# KidSize.net
KiCad netlist of a schematic drawn in EAGLE
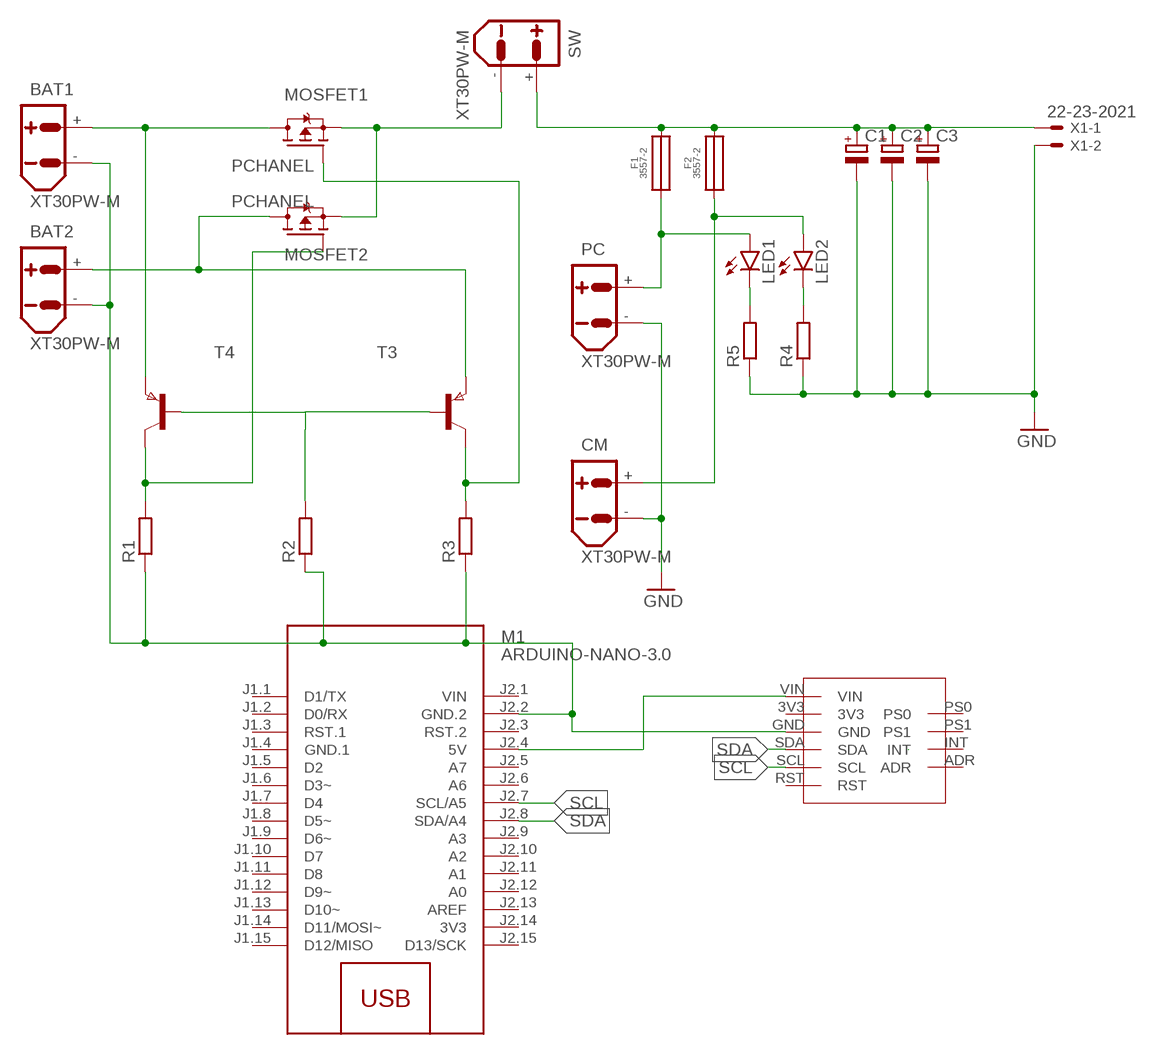
[diagram p0: schematic, sheet 1]

(export (version "E")
  (design (tool "Eeschema 10.0.6"))
  (components
    (comp (ref "BAT1")
      (value "XT30PW-M")
      (footprint "eagle-import:XT30PW-M")
      (libsource (lib "eagle-import") (part "XT30PW-M"))
    )
    (comp (ref "BAT2")
      (value "XT30PW-M")
      (footprint "eagle-import:XT30PW-M")
      (libsource (lib "eagle-import") (part "XT30PW-M"))
    )
    (comp (ref "C1")
      (value "CPOL-EU150CLZ-1014")
      (footprint "eagle-import:150CLZ-1014")
      (libsource (lib "eagle-import") (part "CPOL-EU150CLZ-1014"))
    )
    (comp (ref "C2")
      (value "CPOL-EU150CLZ-1014")
      (footprint "eagle-import:150CLZ-1014")
      (libsource (lib "eagle-import") (part "CPOL-EU150CLZ-1014"))
    )
    (comp (ref "C3")
      (value "CPOL-EU150CLZ-1014")
      (footprint "eagle-import:150CLZ-1014")
      (libsource (lib "eagle-import") (part "CPOL-EU150CLZ-1014"))
    )
    (comp (ref "CM")
      (value "XT30PW-M")
      (footprint "eagle-import:XT30PW-M")
      (libsource (lib "eagle-import") (part "XT30PW-M"))
    )
    (comp (ref "F1")
      (value "3557-2")
      (footprint "eagle-import:3557-2")
      (libsource (lib "eagle-import") (part "3557-2"))
    )
    (comp (ref "F2")
      (value "3557-2")
      (footprint "eagle-import:3557-2")
      (libsource (lib "eagle-import") (part "3557-2"))
    )
    (comp (ref "LED1")
      (value "LEDCHIP-LED0805")
      (footprint "eagle-import:CHIP-LED0805")
      (libsource (lib "eagle-import") (part "LEDCHIP-LED0805"))
    )
    (comp (ref "LED2")
      (value "LEDCHIP-LED0805")
      (footprint "eagle-import:CHIP-LED0805")
      (libsource (lib "eagle-import") (part "LEDCHIP-LED0805"))
    )
    (comp (ref "M1")
      (value "ARDUINO-NANO-3.0")
      (footprint "eagle-import:ARDUINO-NANO-3.0")
      (libsource (lib "eagle-import") (part "ARDUINO-NANO-3.0"))
    )
    (comp (ref "MOSFET1")
      (value "PCHANEL")
      (footprint "eagle-import:TO252")
      (libsource (lib "eagle-import") (part "FDD4141TO252"))
    )
    (comp (ref "MOSFET2")
      (value "PCHANEL")
      (footprint "eagle-import:TO252")
      (libsource (lib "eagle-import") (part "FDD4141TO252"))
    )
    (comp (ref "PC")
      (value "XT30PW-M")
      (footprint "eagle-import:XT30PW-M")
      (libsource (lib "eagle-import") (part "XT30PW-M"))
    )
    (comp (ref "R1")
      (value "R-EU_R1206")
      (footprint "eagle-import:R1206")
      (libsource (lib "eagle-import") (part "R-EU_R1206"))
    )
    (comp (ref "R2")
      (value "R-EU_R1206")
      (footprint "eagle-import:R1206")
      (libsource (lib "eagle-import") (part "R-EU_R1206"))
    )
    (comp (ref "R3")
      (value "R-EU_R1206")
      (footprint "eagle-import:R1206")
      (libsource (lib "eagle-import") (part "R-EU_R1206"))
    )
    (comp (ref "R4")
      (value "R-EU_M0805")
      (footprint "eagle-import:M0805")
      (libsource (lib "eagle-import") (part "R-EU_M0805"))
    )
    (comp (ref "R5")
      (value "R-EU_M0805")
      (footprint "eagle-import:M0805")
      (libsource (lib "eagle-import") (part "R-EU_M0805"))
    )
    (comp (ref "SW")
      (value "XT30PW-M")
      (footprint "eagle-import:XT30PW-M")
      (libsource (lib "eagle-import") (part "XT30PW-M"))
    )
    (comp (ref "T3")
      (value "PNPSOT23")
      (footprint "eagle-import:SOT-23")
      (fields (field (name "MPN") "DSS20200L-7"))
      (libsource (lib "eagle-import") (part "PNPSOT23"))
    )
    (comp (ref "T4")
      (value "PNPSOT23")
      (footprint "eagle-import:SOT-23")
      (fields (field (name "MPN") "DSS20200L-7"))
      (libsource (lib "eagle-import") (part "PNPSOT23"))
    )
    (comp (ref "U$1")
      (value "BNO055_BNO055")
      (footprint "eagle-import:BNO055_BNO055")
      (libsource (lib "eagle-import") (part "BNO055_BNO055"))
    )
    (comp (ref "X1")
      (value "22-23-2021")
      (footprint "eagle-import:22-23-2021")
      (fields (field (name "MF") "MOLEX"))
      (libsource (lib "eagle-import") (part "22-23-2021"))
    )
  )
  (nets
    (net (code "1") (name "/3V3") (class "Default")
      (node (ref "M1") (pin "J2.14") (pinfunction "3V3_J2.14") (pintype "power_in"))
    )
    (net (code "2") (name "/GND.1") (class "Default")
      (node (ref "M1") (pin "J1.4") (pinfunction "GND.1_J1.4") (pintype "power_in"))
    )
    (net (code "3") (name "/VIN") (class "Default")
      (node (ref "M1") (pin "J2.1") (pinfunction "VIN_J2.1") (pintype "power_in"))
    )
    (net (code "4") (name "GND") (class "Default")
      (node (ref "BAT1") (pin "-") (pinfunction "-_-") (pintype "power_in"))
      (node (ref "BAT2") (pin "-") (pinfunction "-_-") (pintype "power_in"))
      (node (ref "C1") (pin "-") (pinfunction "-_-") (pintype "passive"))
      (node (ref "C2") (pin "-") (pinfunction "-_-") (pintype "passive"))
      (node (ref "C3") (pin "-") (pinfunction "-_-") (pintype "passive"))
      (node (ref "CM") (pin "-") (pinfunction "-_-") (pintype "power_in"))
      (node (ref "M1") (pin "J2.2") (pinfunction "GND.2_J2.2") (pintype "power_in"))
      (node (ref "PC") (pin "-") (pinfunction "-_-") (pintype "power_in"))
      (node (ref "R1") (pin "1") (pinfunction "1_1") (pintype "passive"))
      (node (ref "R2") (pin "1") (pinfunction "1_1") (pintype "passive"))
      (node (ref "R3") (pin "1") (pinfunction "1_1") (pintype "passive"))
      (node (ref "R4") (pin "1") (pinfunction "1_1") (pintype "passive"))
      (node (ref "R5") (pin "1") (pinfunction "1_1") (pintype "passive"))
      (node (ref "U$1") (pin "GND") (pinfunction "GND_GND") (pintype "bidirectional"))
      (node (ref "X1") (pin "2") (pinfunction "S_2") (pintype "passive"))
    )
    (net (code "5") (name "Net-(CM-Pad+)") (class "Default")
      (node (ref "CM") (pin "+") (pinfunction "+_+") (pintype "power_in"))
      (node (ref "F2") (pin "1") (pinfunction "1_1") (pintype "bidirectional"))
      (node (ref "F2") (pin "2") (pinfunction "1_2") (pintype "bidirectional"))
      (node (ref "LED2") (pin "A") (pinfunction "A_A") (pintype "passive"))
    )
    (net (code "6") (name "Net-(F1-1-Pad2)") (class "Default")
      (node (ref "F1") (pin "1") (pinfunction "1_1") (pintype "bidirectional"))
      (node (ref "F1") (pin "2") (pinfunction "1_2") (pintype "bidirectional"))
      (node (ref "LED1") (pin "A") (pinfunction "A_A") (pintype "passive"))
      (node (ref "PC") (pin "+") (pinfunction "+_+") (pintype "power_in"))
    )
    (net (code "7") (name "Net-(LED1-PadC)") (class "Default")
      (node (ref "LED1") (pin "C") (pinfunction "C_C") (pintype "passive"))
      (node (ref "R5") (pin "2") (pinfunction "2_2") (pintype "passive"))
    )
    (net (code "8") (name "Net-(LED2-PadC)") (class "Default")
      (node (ref "LED2") (pin "C") (pinfunction "C_C") (pintype "passive"))
      (node (ref "R4") (pin "2") (pinfunction "2_2") (pintype "passive"))
    )
    (net (code "9") (name "Net-(M1-5V)") (class "Default")
      (node (ref "M1") (pin "J2.4") (pinfunction "5V_J2.4") (pintype "power_in"))
      (node (ref "U$1") (pin "VIN") (pinfunction "VIN_VIN") (pintype "bidirectional"))
    )
    (net (code "10") (name "Net-(MOSFET1-D)") (class "Default")
      (node (ref "BAT1") (pin "+") (pinfunction "+_+") (pintype "power_in"))
      (node (ref "MOSFET1") (pin "3") (pinfunction "D_3") (pintype "passive"))
      (node (ref "T4") (pin "2") (pinfunction "E_2") (pintype "passive"))
    )
    (net (code "11") (name "Net-(MOSFET1-G)") (class "Default")
      (node (ref "MOSFET1") (pin "1") (pinfunction "G_1") (pintype "passive"))
      (node (ref "R3") (pin "2") (pinfunction "2_2") (pintype "passive"))
      (node (ref "T3") (pin "1") (pinfunction "C_1") (pintype "passive"))
    )
    (net (code "12") (name "Net-(MOSFET1-S)") (class "Default")
      (node (ref "MOSFET1") (pin "2") (pinfunction "S_2") (pintype "passive"))
      (node (ref "MOSFET2") (pin "2") (pinfunction "S_2") (pintype "passive"))
      (node (ref "SW") (pin "-") (pinfunction "-_-") (pintype "power_in"))
    )
    (net (code "13") (name "Net-(MOSFET2-D)") (class "Default")
      (node (ref "BAT2") (pin "+") (pinfunction "+_+") (pintype "power_in"))
      (node (ref "MOSFET2") (pin "3") (pinfunction "D_3") (pintype "passive"))
      (node (ref "T3") (pin "2") (pinfunction "E_2") (pintype "passive"))
    )
    (net (code "14") (name "Net-(MOSFET2-G)") (class "Default")
      (node (ref "MOSFET2") (pin "1") (pinfunction "G_1") (pintype "passive"))
      (node (ref "R1") (pin "2") (pinfunction "2_2") (pintype "passive"))
      (node (ref "T4") (pin "1") (pinfunction "C_1") (pintype "passive"))
    )
    (net (code "15") (name "Net-(T3-B)") (class "Default")
      (node (ref "R2") (pin "2") (pinfunction "2_2") (pintype "passive"))
      (node (ref "T3") (pin "3") (pinfunction "B_3") (pintype "passive"))
      (node (ref "T4") (pin "3") (pinfunction "B_3") (pintype "passive"))
    )
    (net (code "16") (name "Net-(X1A-S)") (class "Default")
      (node (ref "C1") (pin "+") (pinfunction "+_+") (pintype "passive"))
      (node (ref "C2") (pin "+") (pinfunction "+_+") (pintype "passive"))
      (node (ref "C3") (pin "+") (pinfunction "+_+") (pintype "passive"))
      (node (ref "F1") (pin "3") (pinfunction "2_3") (pintype "bidirectional"))
      (node (ref "F1") (pin "4") (pinfunction "2_4") (pintype "bidirectional"))
      (node (ref "F2") (pin "3") (pinfunction "2_3") (pintype "bidirectional"))
      (node (ref "F2") (pin "4") (pinfunction "2_4") (pintype "bidirectional"))
      (node (ref "SW") (pin "+") (pinfunction "+_+") (pintype "power_in"))
      (node (ref "X1") (pin "1") (pinfunction "S_1") (pintype "passive"))
    )
    (net (code "17") (name "SCL") (class "Default")
      (node (ref "M1") (pin "J2.7") (pinfunction "SCL/A5_J2.7") (pintype "bidirectional"))
      (node (ref "U$1") (pin "SCL") (pinfunction "SCL_SCL") (pintype "bidirectional"))
    )
    (net (code "18") (name "SDA") (class "Default")
      (node (ref "M1") (pin "J2.8") (pinfunction "SDA/A4_J2.8") (pintype "bidirectional"))
      (node (ref "U$1") (pin "SDA") (pinfunction "SDA_SDA") (pintype "bidirectional"))
    )
    (net (code "19") (name "unconnected-(M1-A0-PadJ2.12)") (class "Default")
      (node (ref "M1") (pin "J2.12") (pinfunction "A0_J2.12") (pintype "bidirectional"))
    )
    (net (code "20") (name "unconnected-(M1-A1-PadJ2.11)") (class "Default")
      (node (ref "M1") (pin "J2.11") (pinfunction "A1_J2.11") (pintype "bidirectional"))
    )
    (net (code "21") (name "unconnected-(M1-A2-PadJ2.10)") (class "Default")
      (node (ref "M1") (pin "J2.10") (pinfunction "A2_J2.10") (pintype "bidirectional"))
    )
    (net (code "22") (name "unconnected-(M1-A3-PadJ2.9)") (class "Default")
      (node (ref "M1") (pin "J2.9") (pinfunction "A3_J2.9") (pintype "bidirectional"))
    )
    (net (code "23") (name "unconnected-(M1-A6-PadJ2.6)") (class "Default")
      (node (ref "M1") (pin "J2.6") (pinfunction "A6_J2.6") (pintype "bidirectional"))
    )
    (net (code "24") (name "unconnected-(M1-A7-PadJ2.5)") (class "Default")
      (node (ref "M1") (pin "J2.5") (pinfunction "A7_J2.5") (pintype "bidirectional"))
    )
    (net (code "25") (name "unconnected-(M1-AREF-PadJ2.13)") (class "Default")
      (node (ref "M1") (pin "J2.13") (pinfunction "AREF_J2.13") (pintype "bidirectional"))
    )
    (net (code "26") (name "unconnected-(M1-D0{slash}RX-PadJ1.2)") (class "Default")
      (node (ref "M1") (pin "J1.2") (pinfunction "D0/RX_J1.2") (pintype "bidirectional"))
    )
    (net (code "27") (name "unconnected-(M1-D1{slash}TX-PadJ1.1)") (class "Default")
      (node (ref "M1") (pin "J1.1") (pinfunction "D1/TX_J1.1") (pintype "bidirectional"))
    )
    (net (code "28") (name "unconnected-(M1-D2-PadJ1.5)") (class "Default")
      (node (ref "M1") (pin "J1.5") (pinfunction "D2_J1.5") (pintype "bidirectional"))
    )
    (net (code "29") (name "unconnected-(M1-D3~{}-PadJ1.6)") (class "Default")
      (node (ref "M1") (pin "J1.6") (pinfunction "D3~{}_J1.6") (pintype "bidirectional"))
    )
    (net (code "30") (name "unconnected-(M1-D4-PadJ1.7)") (class "Default")
      (node (ref "M1") (pin "J1.7") (pinfunction "D4_J1.7") (pintype "bidirectional"))
    )
    (net (code "31") (name "unconnected-(M1-D5~{}-PadJ1.8)") (class "Default")
      (node (ref "M1") (pin "J1.8") (pinfunction "D5~{}_J1.8") (pintype "bidirectional"))
    )
    (net (code "32") (name "unconnected-(M1-D6~{}-PadJ1.9)") (class "Default")
      (node (ref "M1") (pin "J1.9") (pinfunction "D6~{}_J1.9") (pintype "bidirectional"))
    )
    (net (code "33") (name "unconnected-(M1-D7-PadJ1.10)") (class "Default")
      (node (ref "M1") (pin "J1.10") (pinfunction "D7_J1.10") (pintype "bidirectional"))
    )
    (net (code "34") (name "unconnected-(M1-D8-PadJ1.11)") (class "Default")
      (node (ref "M1") (pin "J1.11") (pinfunction "D8_J1.11") (pintype "bidirectional"))
    )
    (net (code "35") (name "unconnected-(M1-D9~{}-PadJ1.12)") (class "Default")
      (node (ref "M1") (pin "J1.12") (pinfunction "D9~{}_J1.12") (pintype "bidirectional"))
    )
    (net (code "36") (name "unconnected-(M1-D10~{}-PadJ1.13)") (class "Default")
      (node (ref "M1") (pin "J1.13") (pinfunction "D10~{}_J1.13") (pintype "bidirectional"))
    )
    (net (code "37") (name "unconnected-(M1-D11{slash}MOSI~{}-PadJ1.14)") (class "Default")
      (node (ref "M1") (pin "J1.14") (pinfunction "D11/MOSI~{}_J1.14") (pintype "bidirectional"))
    )
    (net (code "38") (name "unconnected-(M1-D12{slash}MISO-PadJ1.15)") (class "Default")
      (node (ref "M1") (pin "J1.15") (pinfunction "D12/MISO_J1.15") (pintype "bidirectional"))
    )
    (net (code "39") (name "unconnected-(M1-D13{slash}SCK-PadJ2.15)") (class "Default")
      (node (ref "M1") (pin "J2.15") (pinfunction "D13/SCK_J2.15") (pintype "bidirectional"))
    )
    (net (code "40") (name "unconnected-(M1-RST.1-PadJ1.3)") (class "Default")
      (node (ref "M1") (pin "J1.3") (pinfunction "RST.1_J1.3") (pintype "bidirectional"))
    )
    (net (code "41") (name "unconnected-(M1-RST.2-PadJ2.3)") (class "Default")
      (node (ref "M1") (pin "J2.3") (pinfunction "RST.2_J2.3") (pintype "bidirectional"))
    )
    (net (code "42") (name "unconnected-(U$1-Pad3V3)") (class "Default")
      (node (ref "U$1") (pin "3V3") (pinfunction "3V3_3V3") (pintype "bidirectional"))
    )
    (net (code "43") (name "unconnected-(U$1-PadADR)") (class "Default")
      (node (ref "U$1") (pin "ADR") (pinfunction "ADR_ADR") (pintype "bidirectional"))
    )
    (net (code "44") (name "unconnected-(U$1-PadINT)") (class "Default")
      (node (ref "U$1") (pin "INT") (pinfunction "INT_INT") (pintype "bidirectional"))
    )
    (net (code "45") (name "unconnected-(U$1-PadPS0)") (class "Default")
      (node (ref "U$1") (pin "PS0") (pinfunction "PS0_PS0") (pintype "bidirectional"))
    )
    (net (code "46") (name "unconnected-(U$1-PadPS1)") (class "Default")
      (node (ref "U$1") (pin "PS1") (pinfunction "PS1_PS1") (pintype "bidirectional"))
    )
    (net (code "47") (name "unconnected-(U$1-PadRST)") (class "Default")
      (node (ref "U$1") (pin "RST") (pinfunction "RST_RST") (pintype "bidirectional"))
    )
  )
)
